# Regulated_Linear_Power_Supply.net
KiCad netlist of a schematic drawn in EAGLE
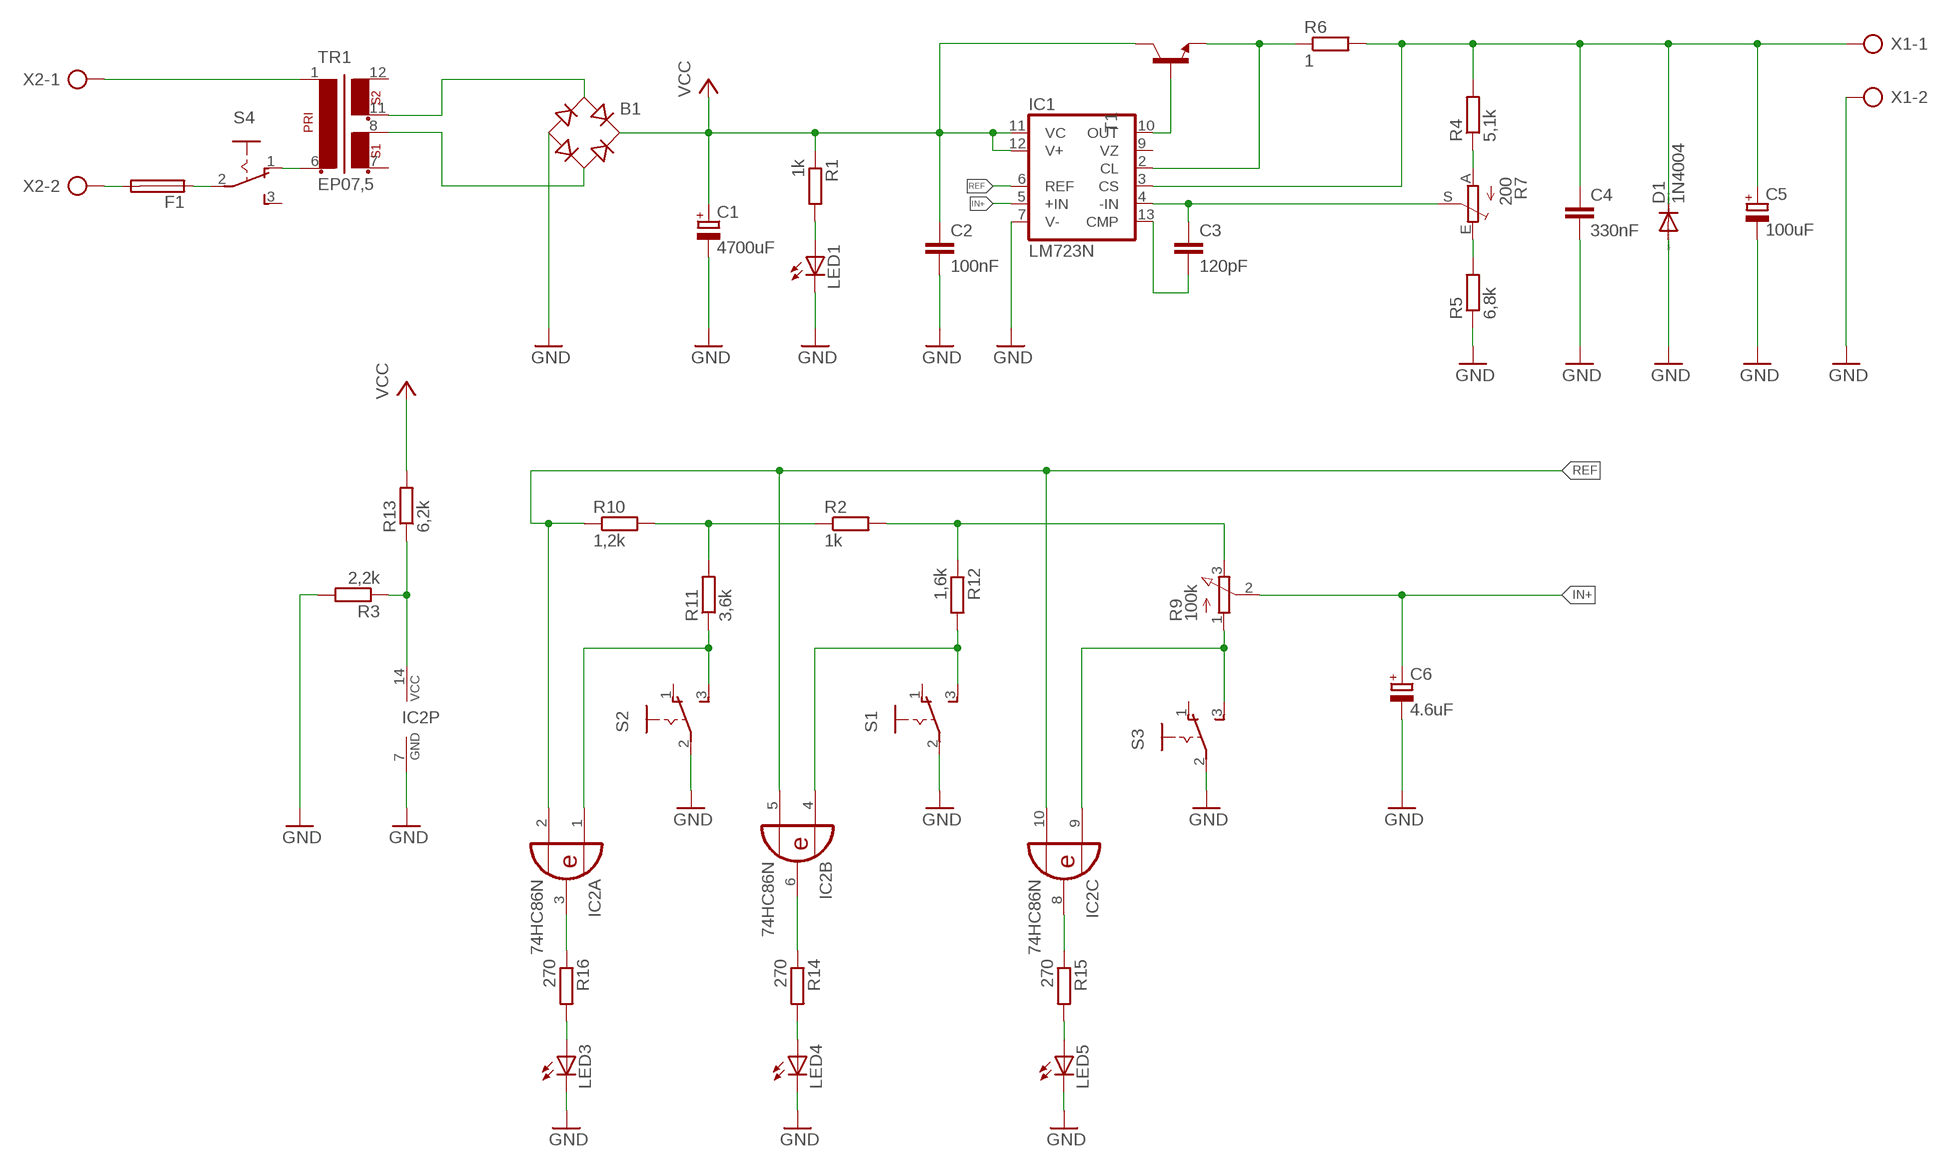
[diagram p0: schematic, sheet 1]

(export (version "E")
  (design (tool "Eeschema 10.0.6"))
  (components
    (comp (ref "B1")
      (value "RB1A")
      (footprint "eagle-import:RB1A")
      (libsource (lib "eagle-import") (part "RB1A"))
    )
    (comp (ref "C1")
      (value "4700uF")
      (footprint "eagle-import:E7,5-16")
      (libsource (lib "eagle-import") (part "CPOL-EUE7.5-16"))
    )
    (comp (ref "C2")
      (value "100nF")
      (footprint "eagle-import:C025-024X044")
      (libsource (lib "eagle-import") (part "C-EU025-024X044"))
    )
    (comp (ref "C3")
      (value "120pF")
      (footprint "eagle-import:C050-024X044")
      (libsource (lib "eagle-import") (part "C-EU050-024X044"))
    )
    (comp (ref "C4")
      (value "330nF")
      (footprint "eagle-import:C050-024X044")
      (libsource (lib "eagle-import") (part "C-EU050-024X044"))
    )
    (comp (ref "C5")
      (value "100uF")
      (footprint "eagle-import:E2,5-6E")
      (libsource (lib "eagle-import") (part "CPOL-EUE2,5-6E"))
    )
    (comp (ref "C6")
      (value "4.6uF")
      (footprint "eagle-import:E2-5")
      (libsource (lib "eagle-import") (part "CPOL-EUE2-5"))
    )
    (comp (ref "D1")
      (value "1N4004")
      (footprint "eagle-import:DO41-10")
      (libsource (lib "eagle-import") (part "1N4004"))
    )
    (comp (ref "F1")
      (value "SH22,5A")
      (footprint "eagle-import:SH22,5A")
      (fields (field (name "MPN") "0031.7701.11"))
      (libsource (lib "eagle-import") (part "SH22,5A"))
    )
    (comp (ref "IC1")
      (value "LM723N")
      (footprint "eagle-import:DIL14")
      (libsource (lib "eagle-import") (part "723NLM"))
    )
    (comp (ref "IC2")
      (value "74HC86N")
      (footprint "eagle-import:DIL14")
      (libsource (lib "eagle-import") (part "7486NHC"))
    )
    (comp (ref "LED1")
      (value "LED5MM")
      (footprint "eagle-import:LED5MM")
      (libsource (lib "eagle-import") (part "LED5MM"))
    )
    (comp (ref "LED3")
      (value "LED5MM")
      (footprint "eagle-import:LED5MM")
      (libsource (lib "eagle-import") (part "LED5MM"))
    )
    (comp (ref "LED4")
      (value "LED5MM")
      (footprint "eagle-import:LED5MM")
      (libsource (lib "eagle-import") (part "LED5MM"))
    )
    (comp (ref "LED5")
      (value "LED5MM")
      (footprint "eagle-import:LED5MM")
      (libsource (lib "eagle-import") (part "LED5MM"))
    )
    (comp (ref "R1")
      (value "1k")
      (footprint "eagle-import:0207_7")
      (libsource (lib "eagle-import") (part "R-EU_0207/7"))
    )
    (comp (ref "R2")
      (value "1k")
      (footprint "eagle-import:0204_7")
      (libsource (lib "eagle-import") (part "R-EU_0204/7"))
    )
    (comp (ref "R3")
      (value "2,2k")
      (footprint "eagle-import:0204_7")
      (libsource (lib "eagle-import") (part "R-EU_0204/7"))
    )
    (comp (ref "R4")
      (value "5,1k")
      (footprint "eagle-import:0204_7")
      (libsource (lib "eagle-import") (part "R-EU_0204/7"))
    )
    (comp (ref "R5")
      (value "6,8k")
      (footprint "eagle-import:0207_7")
      (libsource (lib "eagle-import") (part "R-EU_0207/7"))
    )
    (comp (ref "R6")
      (value "1")
      (footprint "eagle-import:0204_7")
      (libsource (lib "eagle-import") (part "R-EU_0204/7"))
    )
    (comp (ref "R7")
      (value "200")
      (footprint "eagle-import:CA6V")
      (libsource (lib "eagle-import") (part "TRIM_EU-CA6V"))
    )
    (comp (ref "R9")
      (value "100k")
      (footprint "eagle-import:3RP_1610N")
      (libsource (lib "eagle-import") (part "3RP/1610N"))
    )
    (comp (ref "R10")
      (value "1,2k")
      (footprint "eagle-import:0204_7")
      (libsource (lib "eagle-import") (part "R-EU_0204/7"))
    )
    (comp (ref "R11")
      (value "3,6k")
      (footprint "eagle-import:0204_7")
      (libsource (lib "eagle-import") (part "R-EU_0204/7"))
    )
    (comp (ref "R12")
      (value "1,6k")
      (footprint "eagle-import:0204_7")
      (libsource (lib "eagle-import") (part "R-EU_0204/7"))
    )
    (comp (ref "R13")
      (value "6,2k")
      (footprint "eagle-import:0204_7")
      (libsource (lib "eagle-import") (part "R-EU_0204/7"))
    )
    (comp (ref "R14")
      (value "270")
      (footprint "eagle-import:0204_7")
      (libsource (lib "eagle-import") (part "R-EU_0204/7"))
    )
    (comp (ref "R15")
      (value "270")
      (footprint "eagle-import:0204_7")
      (libsource (lib "eagle-import") (part "R-EU_0204/7"))
    )
    (comp (ref "R16")
      (value "270")
      (footprint "eagle-import:0204_7")
      (libsource (lib "eagle-import") (part "R-EU_0204/7"))
    )
    (comp (ref "S1")
      (value "255SB")
      (footprint "eagle-import:255SB")
      (libsource (lib "eagle-import") (part "255SB"))
    )
    (comp (ref "S2")
      (value "255SB")
      (footprint "eagle-import:255SB")
      (libsource (lib "eagle-import") (part "255SB"))
    )
    (comp (ref "S3")
      (value "255SB")
      (footprint "eagle-import:255SB")
      (libsource (lib "eagle-import") (part "255SB"))
    )
    (comp (ref "S4")
      (value "M251")
      (footprint "eagle-import:M251")
      (libsource (lib "eagle-import") (part "M251"))
    )
    (comp (ref "T1")
      (value "-NPN-TO220V")
      (footprint "eagle-import:TO220V")
      (libsource (lib "eagle-import") (part "-NPN-TO220V"))
    )
    (comp (ref "TR1")
      (value "EP07,5")
      (footprint "eagle-import:EP07,5")
      (libsource (lib "eagle-import") (part "EP07,5"))
    )
    (comp (ref "X1")
      (value "AK500/2-H")
      (footprint "eagle-import:AK500_2-H")
      (libsource (lib "eagle-import") (part "AK500/2-H"))
    )
    (comp (ref "X2")
      (value "AK500/2-H")
      (footprint "eagle-import:AK500_2-H")
      (libsource (lib "eagle-import") (part "AK500/2-H"))
    )
  )
  (nets
    (net (code "1") (name "GND") (class "Default")
      (node (ref "B1") (pin "-") (pinfunction "-_-") (pintype "passive"))
      (node (ref "C1") (pin "-") (pinfunction "-_-") (pintype "passive"))
      (node (ref "C2") (pin "2") (pinfunction "2_2") (pintype "passive"))
      (node (ref "C4") (pin "2") (pinfunction "2_2") (pintype "passive"))
      (node (ref "C5") (pin "-") (pinfunction "-_-") (pintype "passive"))
      (node (ref "C6") (pin "-") (pinfunction "-_-") (pintype "passive"))
      (node (ref "D1") (pin "A") (pinfunction "A_A") (pintype "passive"))
      (node (ref "IC1") (pin "7") (pinfunction "V-_7") (pintype "input"))
      (node (ref "IC2") (pin "7") (pinfunction "GND_7") (pintype "power_in"))
      (node (ref "LED1") (pin "K") (pinfunction "C_K") (pintype "passive"))
      (node (ref "LED3") (pin "K") (pinfunction "C_K") (pintype "passive"))
      (node (ref "LED4") (pin "K") (pinfunction "C_K") (pintype "passive"))
      (node (ref "LED5") (pin "K") (pinfunction "C_K") (pintype "passive"))
      (node (ref "R3") (pin "2") (pinfunction "2_2") (pintype "passive"))
      (node (ref "R5") (pin "1") (pinfunction "1_1") (pintype "passive"))
      (node (ref "S1") (pin "2") (pinfunction "P_2") (pintype "passive"))
      (node (ref "S2") (pin "2") (pinfunction "P_2") (pintype "passive"))
      (node (ref "S3") (pin "2") (pinfunction "P_2") (pintype "passive"))
      (node (ref "X1") (pin "2") (pinfunction "KL_2") (pintype "passive"))
    )
    (net (code "2") (name "IN+") (class "Default")
      (node (ref "C6") (pin "+") (pinfunction "+_+") (pintype "passive"))
      (node (ref "IC1") (pin "5") (pinfunction "+IN_5") (pintype "input"))
      (node (ref "R9") (pin "2") (pinfunction "S_2") (pintype "passive"))
    )
    (net (code "3") (name "Net-(IC1--IN)") (class "Default")
      (node (ref "C3") (pin "1") (pinfunction "1_1") (pintype "passive"))
      (node (ref "IC1") (pin "4") (pinfunction "-IN_4") (pintype "input"))
      (node (ref "R7") (pin "S") (pinfunction "S_S") (pintype "passive"))
    )
    (net (code "4") (name "Net-(IC1-CL)") (class "Default")
      (node (ref "IC1") (pin "2") (pinfunction "CL_2") (pintype "input"))
      (node (ref "R6") (pin "1") (pinfunction "1_1") (pintype "passive"))
      (node (ref "T1") (pin "3") (pinfunction "E_3") (pintype "passive"))
    )
    (net (code "5") (name "Net-(IC1-CMP)") (class "Default")
      (node (ref "C3") (pin "2") (pinfunction "2_2") (pintype "passive"))
      (node (ref "IC1") (pin "13") (pinfunction "CMP_13") (pintype "passive"))
    )
    (net (code "6") (name "Net-(IC1-CS)") (class "Default")
      (node (ref "C4") (pin "1") (pinfunction "1_1") (pintype "passive"))
      (node (ref "C5") (pin "+") (pinfunction "+_+") (pintype "passive"))
      (node (ref "D1") (pin "C") (pinfunction "C_C") (pintype "passive"))
      (node (ref "IC1") (pin "3") (pinfunction "CS_3") (pintype "input"))
      (node (ref "R4") (pin "2") (pinfunction "2_2") (pintype "passive"))
      (node (ref "R6") (pin "2") (pinfunction "2_2") (pintype "passive"))
      (node (ref "X1") (pin "1") (pinfunction "KL_1") (pintype "passive"))
    )
    (net (code "7") (name "Net-(IC1-OUT)") (class "Default")
      (node (ref "IC1") (pin "10") (pinfunction "OUT_10") (pintype "output"))
      (node (ref "T1") (pin "1") (pinfunction "B_1") (pintype "passive"))
    )
    (net (code "8") (name "Net-(IC2A-I0)") (class "Default")
      (node (ref "IC2") (pin "1") (pinfunction "I0_1") (pintype "input"))
      (node (ref "R11") (pin "1") (pinfunction "1_1") (pintype "passive"))
      (node (ref "S2") (pin "3") (pinfunction "S_3") (pintype "passive"))
    )
    (net (code "9") (name "Net-(IC2A-O)") (class "Default")
      (node (ref "IC2") (pin "3") (pinfunction "O_3") (pintype "output"))
      (node (ref "R16") (pin "1") (pinfunction "1_1") (pintype "passive"))
    )
    (net (code "10") (name "Net-(IC2B-I0)") (class "Default")
      (node (ref "IC2") (pin "4") (pinfunction "I0_4") (pintype "input"))
      (node (ref "R12") (pin "2") (pinfunction "2_2") (pintype "passive"))
      (node (ref "S1") (pin "3") (pinfunction "S_3") (pintype "passive"))
    )
    (net (code "11") (name "Net-(IC2B-O)") (class "Default")
      (node (ref "IC2") (pin "6") (pinfunction "O_6") (pintype "output"))
      (node (ref "R14") (pin "1") (pinfunction "1_1") (pintype "passive"))
    )
    (net (code "12") (name "Net-(IC2C-I0)") (class "Default")
      (node (ref "IC2") (pin "9") (pinfunction "I0_9") (pintype "input"))
      (node (ref "R9") (pin "1") (pinfunction "A_1") (pintype "passive"))
      (node (ref "S3") (pin "3") (pinfunction "S_3") (pintype "passive"))
    )
    (net (code "13") (name "Net-(IC2C-O)") (class "Default")
      (node (ref "IC2") (pin "8") (pinfunction "O_8") (pintype "output"))
      (node (ref "R15") (pin "1") (pinfunction "1_1") (pintype "passive"))
    )
    (net (code "14") (name "Net-(IC2E-VCC)") (class "Default")
      (node (ref "IC2") (pin "14") (pinfunction "VCC_14") (pintype "power_in"))
      (node (ref "R13") (pin "1") (pinfunction "1_1") (pintype "passive"))
      (node (ref "R3") (pin "1") (pinfunction "1_1") (pintype "passive"))
    )
    (net (code "15") (name "Net-(LED1-PadA)") (class "Default")
      (node (ref "LED1") (pin "A") (pinfunction "A_A") (pintype "passive"))
      (node (ref "R1") (pin "2") (pinfunction "2_2") (pintype "passive"))
    )
    (net (code "16") (name "Net-(LED3-PadA)") (class "Default")
      (node (ref "LED3") (pin "A") (pinfunction "A_A") (pintype "passive"))
      (node (ref "R16") (pin "2") (pinfunction "2_2") (pintype "passive"))
    )
    (net (code "17") (name "Net-(LED4-PadA)") (class "Default")
      (node (ref "LED4") (pin "A") (pinfunction "A_A") (pintype "passive"))
      (node (ref "R14") (pin "2") (pinfunction "2_2") (pintype "passive"))
    )
    (net (code "18") (name "Net-(LED5-PadA)") (class "Default")
      (node (ref "LED5") (pin "A") (pinfunction "A_A") (pintype "passive"))
      (node (ref "R15") (pin "2") (pinfunction "2_2") (pintype "passive"))
    )
    (net (code "19") (name "Net-(R4-Pad1)") (class "Default")
      (node (ref "R4") (pin "1") (pinfunction "1_1") (pintype "passive"))
      (node (ref "R7") (pin "A") (pinfunction "A_A") (pintype "passive"))
    )
    (net (code "20") (name "Net-(R5-Pad2)") (class "Default")
      (node (ref "R5") (pin "2") (pinfunction "2_2") (pintype "passive"))
      (node (ref "R7") (pin "E") (pinfunction "E_E") (pintype "passive"))
    )
    (net (code "21") (name "Net-(R9-E)") (class "Default")
      (node (ref "R12") (pin "1") (pinfunction "1_1") (pintype "passive"))
      (node (ref "R2") (pin "2") (pinfunction "2_2") (pintype "passive"))
      (node (ref "R9") (pin "3") (pinfunction "E_3") (pintype "passive"))
    )
    (net (code "22") (name "Net-(R10-Pad2)") (class "Default")
      (node (ref "R10") (pin "2") (pinfunction "2_2") (pintype "passive"))
      (node (ref "R11") (pin "2") (pinfunction "2_2") (pintype "passive"))
      (node (ref "R2") (pin "1") (pinfunction "1_1") (pintype "passive"))
    )
    (net (code "23") (name "Net-(S4-O)") (class "Default")
      (node (ref "S4") (pin "1") (pinfunction "O_1") (pintype "passive"))
      (node (ref "TR1") (pin "6") (pinfunction "2_6") (pintype "passive"))
    )
    (net (code "24") (name "Net-(S4-P)") (class "Default")
      (node (ref "F1") (pin "1") (pinfunction "1_1") (pintype "passive"))
      (node (ref "S4") (pin "2") (pinfunction "P_2") (pintype "passive"))
    )
    (net (code "25") (name "Net-(TR1-4)") (class "Default")
      (node (ref "B1") (pin "AC2") (pinfunction "AC2_AC2") (pintype "passive"))
      (node (ref "TR1") (pin "8") (pinfunction "4_8") (pintype "passive"))
    )
    (net (code "26") (name "Net-(TR1-5)") (class "Default")
      (node (ref "B1") (pin "AC1") (pinfunction "AC1_AC1") (pintype "passive"))
      (node (ref "TR1") (pin "11") (pinfunction "5_11") (pintype "passive"))
    )
    (net (code "27") (name "Net-(X2A-KL)") (class "Default")
      (node (ref "TR1") (pin "1") (pinfunction "1_1") (pintype "passive"))
      (node (ref "X2") (pin "1") (pinfunction "KL_1") (pintype "passive"))
    )
    (net (code "28") (name "Net-(X2B-KL)") (class "Default")
      (node (ref "F1") (pin "2") (pinfunction "2_2") (pintype "passive"))
      (node (ref "X2") (pin "2") (pinfunction "KL_2") (pintype "passive"))
    )
    (net (code "29") (name "REF") (class "Default")
      (node (ref "IC1") (pin "6") (pinfunction "REF_6") (pintype "output"))
      (node (ref "IC2") (pin "10") (pinfunction "I1_10") (pintype "input"))
      (node (ref "IC2") (pin "2") (pinfunction "I1_2") (pintype "input"))
      (node (ref "IC2") (pin "5") (pinfunction "I1_5") (pintype "input"))
      (node (ref "R10") (pin "1") (pinfunction "1_1") (pintype "passive"))
    )
    (net (code "30") (name "VCC") (class "Default")
      (node (ref "B1") (pin "+") (pinfunction "+_+") (pintype "passive"))
      (node (ref "C1") (pin "+") (pinfunction "+_+") (pintype "passive"))
      (node (ref "C2") (pin "1") (pinfunction "1_1") (pintype "passive"))
      (node (ref "IC1") (pin "11") (pinfunction "VC_11") (pintype "input"))
      (node (ref "IC1") (pin "12") (pinfunction "V+_12") (pintype "input"))
      (node (ref "R1") (pin "1") (pinfunction "1_1") (pintype "passive"))
      (node (ref "R13") (pin "2") (pinfunction "2_2") (pintype "passive"))
      (node (ref "T1") (pin "2") (pinfunction "C_2") (pintype "passive"))
    )
    (net (code "31") (name "unconnected-(IC1-VZ-Pad9)") (class "Default")
      (node (ref "IC1") (pin "9") (pinfunction "VZ_9") (pintype "output"))
    )
    (net (code "32") (name "unconnected-(S1-O-Pad1)") (class "Default")
      (node (ref "S1") (pin "1") (pinfunction "O_1") (pintype "passive"))
    )
    (net (code "33") (name "unconnected-(S2-O-Pad1)") (class "Default")
      (node (ref "S2") (pin "1") (pinfunction "O_1") (pintype "passive"))
    )
    (net (code "34") (name "unconnected-(S3-O-Pad1)") (class "Default")
      (node (ref "S3") (pin "1") (pinfunction "O_1") (pintype "passive"))
    )
    (net (code "35") (name "unconnected-(S4-S-Pad3)") (class "Default")
      (node (ref "S4") (pin "3") (pinfunction "S_3") (pintype "passive"))
    )
    (net (code "36") (name "unconnected-(TR1-3-Pad7)") (class "Default")
      (node (ref "TR1") (pin "7") (pinfunction "3_7") (pintype "passive"))
    )
    (net (code "37") (name "unconnected-(TR1-6-Pad12)") (class "Default")
      (node (ref "TR1") (pin "12") (pinfunction "6_12") (pintype "passive"))
    )
  )
)
